# STM32L441CE.net
KiCad netlist of a schematic drawn in EAGLE
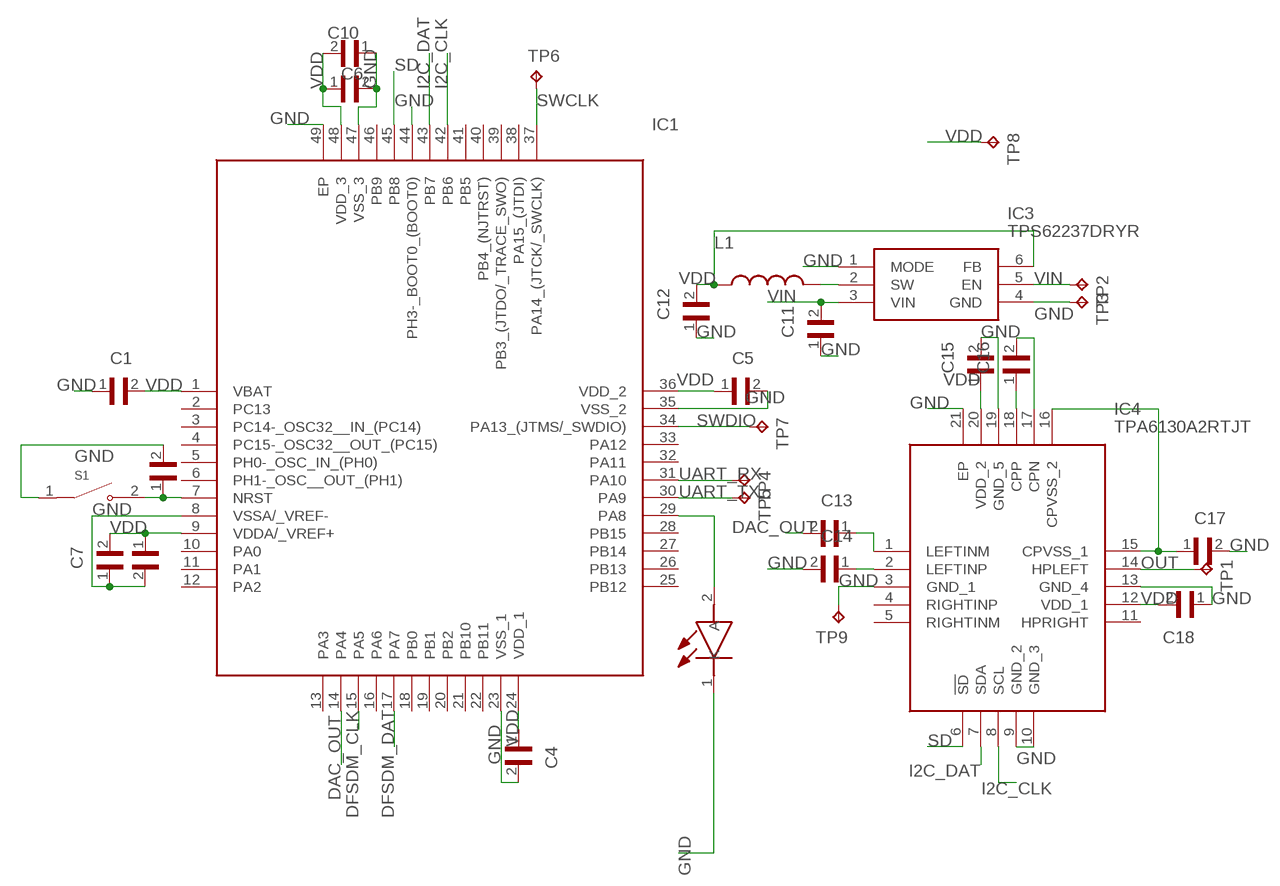
[diagram p0: schematic, sheet 1]
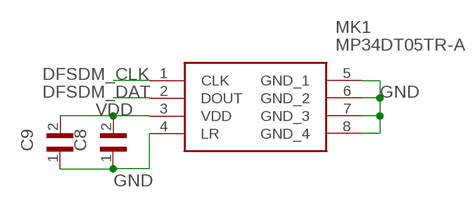
[diagram p1: schematic, sheet 2]

(export (version "E")
  (design (tool "Eeschema 10.0.6"))
  (components
    (comp (ref "C1")
      (value "GRM033C80J104KE15D")
      (footprint "eagle-import:CAPC0603X33N")
      (fields (field (name "DIGI-KEY_PART_NUMBER") "490-10390-1-ND") (field (name "MF") "Murata Electronics"))
      (libsource (lib "eagle-import") (part "GRM033C80J104KE15D"))
    )
    (comp (ref "C2")
      (value "GRM033C80J104KE15D")
      (footprint "eagle-import:CAPC0603X33N")
      (fields (field (name "DIGI-KEY_PART_NUMBER") "490-10390-1-ND") (field (name "MF") "Murata Electronics"))
      (libsource (lib "eagle-import") (part "GRM033C80J104KE15D"))
    )
    (comp (ref "C3")
      (value "GRM033C80J104KE15D")
      (footprint "eagle-import:CAPC0603X33N")
      (fields (field (name "DIGI-KEY_PART_NUMBER") "490-10390-1-ND") (field (name "MF") "Murata Electronics"))
      (libsource (lib "eagle-import") (part "GRM033C80J104KE15D"))
    )
    (comp (ref "C4")
      (value "GRM033C80J104KE15D")
      (footprint "eagle-import:CAPC0603X33N")
      (fields (field (name "DIGI-KEY_PART_NUMBER") "490-10390-1-ND") (field (name "MF") "Murata Electronics"))
      (libsource (lib "eagle-import") (part "GRM033C80J104KE15D"))
    )
    (comp (ref "C5")
      (value "GRM033C80J104KE15D")
      (footprint "eagle-import:CAPC0603X33N")
      (fields (field (name "DIGI-KEY_PART_NUMBER") "490-10390-1-ND") (field (name "MF") "Murata Electronics"))
      (libsource (lib "eagle-import") (part "GRM033C80J104KE15D"))
    )
    (comp (ref "C6")
      (value "GRM033C80J104KE15D")
      (footprint "eagle-import:CAPC0603X33N")
      (fields (field (name "DIGI-KEY_PART_NUMBER") "490-10390-1-ND") (field (name "MF") "Murata Electronics"))
      (libsource (lib "eagle-import") (part "GRM033C80J104KE15D"))
    )
    (comp (ref "C7")
      (value "JMK105C6105KV-F")
      (footprint "eagle-import:CAPC1005X55N")
      (fields (field (name "DIGI-KEY_PART_NUMBER") "587-3381-1-ND") (field (name "MF") "Taiyo Yuden"))
      (libsource (lib "eagle-import") (part "JMK105C6105KV-F"))
    )
    (comp (ref "C10")
      (value "GRM155R60J475ME47D")
      (footprint "eagle-import:CAPC1005X60N")
      (fields (field (name "DIGI-KEY_PART_NUMBER") "490-5915-1-ND") (field (name "MF") "Murata"))
      (libsource (lib "eagle-import") (part "GRM155R60J475ME47D"))
    )
    (comp (ref "C11")
      (value "GRM155R60J225KE95D")
      (footprint "eagle-import:CAPC1005X55N")
      (fields (field (name "DIGI-KEY_PART_NUMBER") "490-12532-1-ND") (field (name "MF") "Murata"))
      (libsource (lib "eagle-import") (part "GRM155R60J225KE95D"))
    )
    (comp (ref "C12")
      (value "GRM155R60J475ME47D")
      (footprint "eagle-import:CAPC1005X60N")
      (fields (field (name "DIGI-KEY_PART_NUMBER") "490-5915-1-ND") (field (name "MF") "Murata"))
      (libsource (lib "eagle-import") (part "GRM155R60J475ME47D"))
    )
    (comp (ref "C13")
      (value "CC0402KRX5R5BB474")
      (footprint "eagle-import:CAPC1005X55N")
      (fields (field (name "DIGI-KEY_PART_NUMBER") "311-1684-1-ND") (field (name "MF") "Yageo"))
      (libsource (lib "eagle-import") (part "CC0402KRX5R5BB474"))
    )
    (comp (ref "C14")
      (value "CC0402KRX5R5BB474")
      (footprint "eagle-import:CAPC1005X55N")
      (fields (field (name "DIGI-KEY_PART_NUMBER") "311-1684-1-ND") (field (name "MF") "Yageo"))
      (libsource (lib "eagle-import") (part "CC0402KRX5R5BB474"))
    )
    (comp (ref "C15")
      (value "JMK105C6105KV-F")
      (footprint "eagle-import:CAPC1005X55N")
      (fields (field (name "DIGI-KEY_PART_NUMBER") "587-3381-1-ND") (field (name "MF") "Taiyo Yuden"))
      (libsource (lib "eagle-import") (part "JMK105C6105KV-F"))
    )
    (comp (ref "C16")
      (value "JMK105C6105KV-F")
      (footprint "eagle-import:CAPC1005X55N")
      (fields (field (name "DIGI-KEY_PART_NUMBER") "587-3381-1-ND") (field (name "MF") "Taiyo Yuden"))
      (libsource (lib "eagle-import") (part "JMK105C6105KV-F"))
    )
    (comp (ref "C17")
      (value "JMK105C6105KV-F")
      (footprint "eagle-import:CAPC1005X55N")
      (fields (field (name "DIGI-KEY_PART_NUMBER") "587-3381-1-ND") (field (name "MF") "Taiyo Yuden"))
      (libsource (lib "eagle-import") (part "JMK105C6105KV-F"))
    )
    (comp (ref "C18")
      (value "JMK105C6105KV-F")
      (footprint "eagle-import:CAPC1005X55N")
      (fields (field (name "DIGI-KEY_PART_NUMBER") "587-3381-1-ND") (field (name "MF") "Taiyo Yuden"))
      (libsource (lib "eagle-import") (part "JMK105C6105KV-F"))
    )
    (comp (ref "IC1")
      (value "STM32L451CEU6")
      (footprint "eagle-import:QFN50P700X700X60-49N")
      (fields (field (name "MOUSER_PART_NUMBER") "511-STM32L451CEU6"))
      (libsource (lib "eagle-import") (part "STM32L451CEU6"))
    )
    (comp (ref "IC3")
      (value "TPS62237DRYR")
      (footprint "eagle-import:SON50P100X145X60-6N")
      (fields (field (name "MOUSER_PART_NUMBER") "595-TPS62237DRYR"))
      (libsource (lib "eagle-import") (part "TPS62237DRYR"))
    )
    (comp (ref "IC4")
      (value "TPA6130A2RTJT")
      (footprint "eagle-import:QFN50P400X400X80-21N")
      (fields (field (name "MOUSER_PART_NUMBER") "595-TPA6130A2RTJT"))
      (libsource (lib "eagle-import") (part "TPA6130A2RTJT"))
    )
    (comp (ref "L1")
      (value "LQM21PN2R2MC0D")
      (footprint "eagle-import:INDC2012X55N")
      (fields (field (name "DIGI-KEY_PART_NUMBER") "490-4994-1-ND") (field (name "MF") "Murata"))
      (libsource (lib "eagle-import") (part "LQM21PN2R2MC0D"))
    )
    (comp (ref "LED1")
      (value "VLMS1500-GS08")
      (footprint "eagle-import:VLMG1500GS08")
      (fields (field (name "MOUSER_PART_NUMBER") "78-VLMS1500-GS08"))
      (libsource (lib "eagle-import") (part "VLMS1500-GS08"))
    )
    (comp (ref "S1")
      (value "B3U-1000P")
      (footprint "eagle-import:SW_B3U-1000P")
      (fields (field (name "DIGI-KEY_PART_NUMBER") "SW1020CT-ND") (field (name "MF") "Omron"))
      (libsource (lib "eagle-import") (part "B3U-1000P"))
    )
    (comp (ref "TP1")
      (value "TPTP11R")
      (footprint "eagle-import:TP11R")
      (libsource (lib "eagle-import") (part "TPTP11R"))
    )
    (comp (ref "TP2")
      (value "TPTP11R")
      (footprint "eagle-import:TP11R")
      (libsource (lib "eagle-import") (part "TPTP11R"))
    )
    (comp (ref "TP3")
      (value "TPTP11R")
      (footprint "eagle-import:TP11R")
      (libsource (lib "eagle-import") (part "TPTP11R"))
    )
    (comp (ref "TP4")
      (value "TPTP11R")
      (footprint "eagle-import:TP11R")
      (libsource (lib "eagle-import") (part "TPTP11R"))
    )
    (comp (ref "TP5")
      (value "TPTP11R")
      (footprint "eagle-import:TP11R")
      (libsource (lib "eagle-import") (part "TPTP11R"))
    )
    (comp (ref "TP6")
      (value "TPTP11R")
      (footprint "eagle-import:TP11R")
      (libsource (lib "eagle-import") (part "TPTP11R"))
    )
    (comp (ref "TP7")
      (value "TPTP11R")
      (footprint "eagle-import:TP11R")
      (libsource (lib "eagle-import") (part "TPTP11R"))
    )
    (comp (ref "TP8")
      (value "TPTP11R")
      (footprint "eagle-import:TP11R")
      (libsource (lib "eagle-import") (part "TPTP11R"))
    )
    (comp (ref "TP9")
      (value "TPTP11R")
      (footprint "eagle-import:TP11R")
      (libsource (lib "eagle-import") (part "TPTP11R"))
    )
    (comp (ref "C8")
      (value "JMK105C6105KV-F")
      (footprint "eagle-import:CAPC1005X55N")
      (fields (field (name "DIGI-KEY_PART_NUMBER") "587-3381-1-ND") (field (name "MF") "Taiyo Yuden"))
      (libsource (lib "eagle-import") (part "JMK105C6105KV-F"))
    )
    (comp (ref "C9")
      (value "GRM033C80J104KE15D")
      (footprint "eagle-import:CAPC0603X33N")
      (fields (field (name "DIGI-KEY_PART_NUMBER") "490-10390-1-ND") (field (name "MF") "Murata Electronics"))
      (libsource (lib "eagle-import") (part "GRM033C80J104KE15D"))
    )
    (comp (ref "MK1")
      (value "MP34DT05TR-A")
      (footprint "eagle-import:MP34DT05TRA")
      (fields (field (name "MOUSER_PART_NUMBER") "511-MP34DT05TR-A"))
      (libsource (lib "eagle-import") (part "MP34DT05TR-A"))
    )
  )
  (nets
    (net (code "1") (name "DAC_OUT") (class "Default")
      (node (ref "C13") (pin "2") (pinfunction "2_2") (pintype "passive"))
      (node (ref "IC1") (pin "14") (pinfunction "PA4_14") (pintype "bidirectional"))
    )
    (net (code "2") (name "DFSDM_CLK") (class "Default")
      (node (ref "IC1") (pin "15") (pinfunction "PA5_15") (pintype "bidirectional"))
      (node (ref "MK1") (pin "1") (pinfunction "CLK_1") (pintype "bidirectional"))
    )
    (net (code "3") (name "DFSDM_DAT") (class "Default")
      (node (ref "IC1") (pin "17") (pinfunction "PA7_17") (pintype "bidirectional"))
      (node (ref "MK1") (pin "2") (pinfunction "DOUT_2") (pintype "bidirectional"))
    )
    (net (code "4") (name "GND") (class "Default")
      (node (ref "C1") (pin "1") (pinfunction "1_1") (pintype "passive"))
      (node (ref "C10") (pin "1") (pinfunction "1_1") (pintype "passive"))
      (node (ref "C11") (pin "1") (pinfunction "1_1") (pintype "passive"))
      (node (ref "C12") (pin "1") (pinfunction "1_1") (pintype "passive"))
      (node (ref "C14") (pin "2") (pinfunction "2_2") (pintype "passive"))
      (node (ref "C15") (pin "2") (pinfunction "2_2") (pintype "passive"))
      (node (ref "C17") (pin "2") (pinfunction "2_2") (pintype "passive"))
      (node (ref "C18") (pin "1") (pinfunction "1_1") (pintype "passive"))
      (node (ref "C2") (pin "2") (pinfunction "2_2") (pintype "passive"))
      (node (ref "C3") (pin "2") (pinfunction "2_2") (pintype "passive"))
      (node (ref "C4") (pin "2") (pinfunction "2_2") (pintype "passive"))
      (node (ref "C5") (pin "2") (pinfunction "2_2") (pintype "passive"))
      (node (ref "C6") (pin "2") (pinfunction "2_2") (pintype "passive"))
      (node (ref "C7") (pin "1") (pinfunction "1_1") (pintype "passive"))
      (node (ref "C8") (pin "1") (pinfunction "1_1") (pintype "passive"))
      (node (ref "C9") (pin "1") (pinfunction "1_1") (pintype "passive"))
      (node (ref "IC1") (pin "23") (pinfunction "VSS_1_23") (pintype "bidirectional"))
      (node (ref "IC1") (pin "35") (pinfunction "VSS_2_35") (pintype "bidirectional"))
      (node (ref "IC1") (pin "44") (pinfunction "PH3-_BOOT0_(BOOT0)_44") (pintype "bidirectional"))
      (node (ref "IC1") (pin "47") (pinfunction "VSS_3_47") (pintype "bidirectional"))
      (node (ref "IC1") (pin "49") (pinfunction "EP_49") (pintype "bidirectional"))
      (node (ref "IC1") (pin "8") (pinfunction "VSSA/_VREF-_8") (pintype "bidirectional"))
      (node (ref "IC3") (pin "1") (pinfunction "MODE_1") (pintype "bidirectional"))
      (node (ref "IC3") (pin "4") (pinfunction "GND_4") (pintype "bidirectional"))
      (node (ref "IC4") (pin "10") (pinfunction "GND_3_10") (pintype "bidirectional"))
      (node (ref "IC4") (pin "13") (pinfunction "GND_4_13") (pintype "bidirectional"))
      (node (ref "IC4") (pin "19") (pinfunction "GND_5_19") (pintype "bidirectional"))
      (node (ref "IC4") (pin "21") (pinfunction "EP_21") (pintype "bidirectional"))
      (node (ref "IC4") (pin "3") (pinfunction "GND_1_3") (pintype "bidirectional"))
      (node (ref "IC4") (pin "9") (pinfunction "GND_2_9") (pintype "bidirectional"))
      (node (ref "LED1") (pin "1") (pinfunction "K_1") (pintype "bidirectional"))
      (node (ref "MK1") (pin "4") (pinfunction "LR_4") (pintype "bidirectional"))
      (node (ref "MK1") (pin "5") (pinfunction "GND_1_5") (pintype "bidirectional"))
      (node (ref "MK1") (pin "6") (pinfunction "GND_2_6") (pintype "bidirectional"))
      (node (ref "MK1") (pin "7") (pinfunction "GND_3_7") (pintype "bidirectional"))
      (node (ref "MK1") (pin "8") (pinfunction "GND_4_8") (pintype "bidirectional"))
      (node (ref "S1") (pin "1") (pinfunction "1_1") (pintype "passive"))
      (node (ref "TP3") (pin "TP") (pinfunction "TP_TP") (pintype "input"))
      (node (ref "TP9") (pin "TP") (pinfunction "TP_TP") (pintype "input"))
    )
    (net (code "5") (name "I2C_CLK") (class "Default")
      (node (ref "IC1") (pin "42") (pinfunction "PB6_42") (pintype "bidirectional"))
      (node (ref "IC4") (pin "8") (pinfunction "SCL_8") (pintype "bidirectional"))
    )
    (net (code "6") (name "I2C_DAT") (class "Default")
      (node (ref "IC1") (pin "43") (pinfunction "PB7_43") (pintype "bidirectional"))
      (node (ref "IC4") (pin "7") (pinfunction "SDA_7") (pintype "bidirectional"))
    )
    (net (code "7") (name "Net-(IC1-NRST)") (class "Default")
      (node (ref "C2") (pin "1") (pinfunction "1_1") (pintype "passive"))
      (node (ref "IC1") (pin "7") (pinfunction "NRST_7") (pintype "bidirectional"))
      (node (ref "S1") (pin "2") (pinfunction "2_2") (pintype "passive"))
    )
    (net (code "8") (name "Net-(IC1-PA8)") (class "Default")
      (node (ref "IC1") (pin "29") (pinfunction "PA8_29") (pintype "bidirectional"))
      (node (ref "LED1") (pin "2") (pinfunction "A_2") (pintype "bidirectional"))
    )
    (net (code "9") (name "Net-(IC3-SW)") (class "Default")
      (node (ref "IC3") (pin "2") (pinfunction "SW_2") (pintype "bidirectional"))
      (node (ref "L1") (pin "2") (pinfunction "2_2") (pintype "passive"))
    )
    (net (code "10") (name "Net-(IC4-CPN)") (class "Default")
      (node (ref "C16") (pin "2") (pinfunction "2_2") (pintype "passive"))
      (node (ref "IC4") (pin "17") (pinfunction "CPN_17") (pintype "bidirectional"))
    )
    (net (code "11") (name "Net-(IC4-CPP)") (class "Default")
      (node (ref "C16") (pin "1") (pinfunction "1_1") (pintype "passive"))
      (node (ref "IC4") (pin "18") (pinfunction "CPP_18") (pintype "bidirectional"))
    )
    (net (code "12") (name "Net-(IC4-CPVSS_1)") (class "Default")
      (node (ref "C17") (pin "1") (pinfunction "1_1") (pintype "passive"))
      (node (ref "IC4") (pin "15") (pinfunction "CPVSS_1_15") (pintype "bidirectional"))
      (node (ref "IC4") (pin "16") (pinfunction "CPVSS_2_16") (pintype "bidirectional"))
    )
    (net (code "13") (name "Net-(IC4-LEFTINM)") (class "Default")
      (node (ref "C13") (pin "1") (pinfunction "1_1") (pintype "passive"))
      (node (ref "IC4") (pin "1") (pinfunction "LEFTINM_1") (pintype "bidirectional"))
    )
    (net (code "14") (name "Net-(IC4-LEFTINP)") (class "Default")
      (node (ref "C14") (pin "1") (pinfunction "1_1") (pintype "passive"))
      (node (ref "IC4") (pin "2") (pinfunction "LEFTINP_2") (pintype "bidirectional"))
    )
    (net (code "15") (name "OUT") (class "Default")
      (node (ref "IC4") (pin "14") (pinfunction "HPLEFT_14") (pintype "bidirectional"))
      (node (ref "TP1") (pin "TP") (pinfunction "TP_TP") (pintype "input"))
    )
    (net (code "16") (name "SD") (class "Default")
      (node (ref "IC1") (pin "45") (pinfunction "PB8_45") (pintype "bidirectional"))
      (node (ref "IC4") (pin "6") (pinfunction "~{SD}_6") (pintype "bidirectional"))
    )
    (net (code "17") (name "SWCLK") (class "Default")
      (node (ref "IC1") (pin "37") (pinfunction "PA14_(JTCK/_SWCLK)_37") (pintype "bidirectional"))
      (node (ref "TP6") (pin "TP") (pinfunction "TP_TP") (pintype "input"))
    )
    (net (code "18") (name "SWDIO") (class "Default")
      (node (ref "IC1") (pin "34") (pinfunction "PA13_(JTMS/_SWDIO)_34") (pintype "bidirectional"))
      (node (ref "TP7") (pin "TP") (pinfunction "TP_TP") (pintype "input"))
    )
    (net (code "19") (name "UART_RX") (class "Default")
      (node (ref "IC1") (pin "31") (pinfunction "PA10_31") (pintype "bidirectional"))
      (node (ref "TP4") (pin "TP") (pinfunction "TP_TP") (pintype "input"))
    )
    (net (code "20") (name "UART_TX") (class "Default")
      (node (ref "IC1") (pin "30") (pinfunction "PA9_30") (pintype "bidirectional"))
      (node (ref "TP5") (pin "TP") (pinfunction "TP_TP") (pintype "input"))
    )
    (net (code "21") (name "VDD") (class "Default")
      (node (ref "C1") (pin "2") (pinfunction "2_2") (pintype "passive"))
      (node (ref "C10") (pin "2") (pinfunction "2_2") (pintype "passive"))
      (node (ref "C12") (pin "2") (pinfunction "2_2") (pintype "passive"))
      (node (ref "C15") (pin "1") (pinfunction "1_1") (pintype "passive"))
      (node (ref "C18") (pin "2") (pinfunction "2_2") (pintype "passive"))
      (node (ref "C3") (pin "1") (pinfunction "1_1") (pintype "passive"))
      (node (ref "C4") (pin "1") (pinfunction "1_1") (pintype "passive"))
      (node (ref "C5") (pin "1") (pinfunction "1_1") (pintype "passive"))
      (node (ref "C6") (pin "1") (pinfunction "1_1") (pintype "passive"))
      (node (ref "C7") (pin "2") (pinfunction "2_2") (pintype "passive"))
      (node (ref "C8") (pin "2") (pinfunction "2_2") (pintype "passive"))
      (node (ref "C9") (pin "2") (pinfunction "2_2") (pintype "passive"))
      (node (ref "IC1") (pin "1") (pinfunction "VBAT_1") (pintype "bidirectional"))
      (node (ref "IC1") (pin "24") (pinfunction "VDD_1_24") (pintype "bidirectional"))
      (node (ref "IC1") (pin "36") (pinfunction "VDD_2_36") (pintype "bidirectional"))
      (node (ref "IC1") (pin "48") (pinfunction "VDD_3_48") (pintype "bidirectional"))
      (node (ref "IC1") (pin "9") (pinfunction "VDDA/_VREF+_9") (pintype "bidirectional"))
      (node (ref "IC3") (pin "6") (pinfunction "FB_6") (pintype "bidirectional"))
      (node (ref "IC4") (pin "12") (pinfunction "VDD_1_12") (pintype "bidirectional"))
      (node (ref "IC4") (pin "20") (pinfunction "VDD_2_20") (pintype "bidirectional"))
      (node (ref "L1") (pin "1") (pinfunction "1_1") (pintype "passive"))
      (node (ref "MK1") (pin "3") (pinfunction "VDD_3") (pintype "bidirectional"))
      (node (ref "TP8") (pin "TP") (pinfunction "TP_TP") (pintype "input"))
    )
    (net (code "22") (name "VIN") (class "Default")
      (node (ref "C11") (pin "2") (pinfunction "2_2") (pintype "passive"))
      (node (ref "IC3") (pin "3") (pinfunction "VIN_3") (pintype "bidirectional"))
      (node (ref "IC3") (pin "5") (pinfunction "EN_5") (pintype "bidirectional"))
      (node (ref "TP2") (pin "TP") (pinfunction "TP_TP") (pintype "input"))
    )
    (net (code "23") (name "unconnected-(IC1-PA0-Pad10)") (class "Default")
      (node (ref "IC1") (pin "10") (pinfunction "PA0_10") (pintype "bidirectional"))
    )
    (net (code "24") (name "unconnected-(IC1-PA1-Pad11)") (class "Default")
      (node (ref "IC1") (pin "11") (pinfunction "PA1_11") (pintype "bidirectional"))
    )
    (net (code "25") (name "unconnected-(IC1-PA2-Pad12)") (class "Default")
      (node (ref "IC1") (pin "12") (pinfunction "PA2_12") (pintype "bidirectional"))
    )
    (net (code "26") (name "unconnected-(IC1-PA3-Pad13)") (class "Default")
      (node (ref "IC1") (pin "13") (pinfunction "PA3_13") (pintype "bidirectional"))
    )
    (net (code "27") (name "unconnected-(IC1-PA6-Pad16)") (class "Default")
      (node (ref "IC1") (pin "16") (pinfunction "PA6_16") (pintype "bidirectional"))
    )
    (net (code "28") (name "unconnected-(IC1-PA11-Pad32)") (class "Default")
      (node (ref "IC1") (pin "32") (pinfunction "PA11_32") (pintype "bidirectional"))
    )
    (net (code "29") (name "unconnected-(IC1-PA12-Pad33)") (class "Default")
      (node (ref "IC1") (pin "33") (pinfunction "PA12_33") (pintype "bidirectional"))
    )
    (net (code "30") (name "unconnected-(IC1-PA15_(JTDI)-Pad38)") (class "Default")
      (node (ref "IC1") (pin "38") (pinfunction "PA15_(JTDI)_38") (pintype "bidirectional"))
    )
    (net (code "31") (name "unconnected-(IC1-PB0-Pad18)") (class "Default")
      (node (ref "IC1") (pin "18") (pinfunction "PB0_18") (pintype "bidirectional"))
    )
    (net (code "32") (name "unconnected-(IC1-PB1-Pad19)") (class "Default")
      (node (ref "IC1") (pin "19") (pinfunction "PB1_19") (pintype "bidirectional"))
    )
    (net (code "33") (name "unconnected-(IC1-PB2-Pad20)") (class "Default")
      (node (ref "IC1") (pin "20") (pinfunction "PB2_20") (pintype "bidirectional"))
    )
    (net (code "34") (name "unconnected-(IC1-PB3_(JTDO{slash}_TRACE_SWO)-Pad39)") (class "Default")
      (node (ref "IC1") (pin "39") (pinfunction "PB3_(JTDO/_TRACE_SWO)_39") (pintype "bidirectional"))
    )
    (net (code "35") (name "unconnected-(IC1-PB4_(NJTRST)-Pad40)") (class "Default")
      (node (ref "IC1") (pin "40") (pinfunction "PB4_(NJTRST)_40") (pintype "bidirectional"))
    )
    (net (code "36") (name "unconnected-(IC1-PB5-Pad41)") (class "Default")
      (node (ref "IC1") (pin "41") (pinfunction "PB5_41") (pintype "bidirectional"))
    )
    (net (code "37") (name "unconnected-(IC1-PB9-Pad46)") (class "Default")
      (node (ref "IC1") (pin "46") (pinfunction "PB9_46") (pintype "bidirectional"))
    )
    (net (code "38") (name "unconnected-(IC1-PB10-Pad21)") (class "Default")
      (node (ref "IC1") (pin "21") (pinfunction "PB10_21") (pintype "bidirectional"))
    )
    (net (code "39") (name "unconnected-(IC1-PB11-Pad22)") (class "Default")
      (node (ref "IC1") (pin "22") (pinfunction "PB11_22") (pintype "bidirectional"))
    )
    (net (code "40") (name "unconnected-(IC1-PB12-Pad25)") (class "Default")
      (node (ref "IC1") (pin "25") (pinfunction "PB12_25") (pintype "bidirectional"))
    )
    (net (code "41") (name "unconnected-(IC1-PB13-Pad26)") (class "Default")
      (node (ref "IC1") (pin "26") (pinfunction "PB13_26") (pintype "bidirectional"))
    )
    (net (code "42") (name "unconnected-(IC1-PB14-Pad27)") (class "Default")
      (node (ref "IC1") (pin "27") (pinfunction "PB14_27") (pintype "bidirectional"))
    )
    (net (code "43") (name "unconnected-(IC1-PB15-Pad28)") (class "Default")
      (node (ref "IC1") (pin "28") (pinfunction "PB15_28") (pintype "bidirectional"))
    )
    (net (code "44") (name "unconnected-(IC1-PC13-Pad2)") (class "Default")
      (node (ref "IC1") (pin "2") (pinfunction "PC13_2") (pintype "bidirectional"))
    )
    (net (code "45") (name "unconnected-(IC1-PC14-_OSC32__IN_(PC14)-Pad3)") (class "Default")
      (node (ref "IC1") (pin "3") (pinfunction "PC14-_OSC32__IN_(PC14)_3") (pintype "bidirectional"))
    )
    (net (code "46") (name "unconnected-(IC1-PC15-_OSC32__OUT_(PC15)-Pad4)") (class "Default")
      (node (ref "IC1") (pin "4") (pinfunction "PC15-_OSC32__OUT_(PC15)_4") (pintype "bidirectional"))
    )
    (net (code "47") (name "unconnected-(IC1-PH0-_OSC_IN_(PH0)-Pad5)") (class "Default")
      (node (ref "IC1") (pin "5") (pinfunction "PH0-_OSC_IN_(PH0)_5") (pintype "bidirectional"))
    )
    (net (code "48") (name "unconnected-(IC1-PH1-_OSC__OUT_(PH1)-Pad6)") (class "Default")
      (node (ref "IC1") (pin "6") (pinfunction "PH1-_OSC__OUT_(PH1)_6") (pintype "bidirectional"))
    )
    (net (code "49") (name "unconnected-(IC4-HPRIGHT-Pad11)") (class "Default")
      (node (ref "IC4") (pin "11") (pinfunction "HPRIGHT_11") (pintype "bidirectional"))
    )
    (net (code "50") (name "unconnected-(IC4-RIGHTINM-Pad5)") (class "Default")
      (node (ref "IC4") (pin "5") (pinfunction "RIGHTINM_5") (pintype "bidirectional"))
    )
    (net (code "51") (name "unconnected-(IC4-RIGHTINP-Pad4)") (class "Default")
      (node (ref "IC4") (pin "4") (pinfunction "RIGHTINP_4") (pintype "bidirectional"))
    )
  )
)
